# CurrentSensorInput.net
KiCad netlist of a schematic drawn in Altium Designer
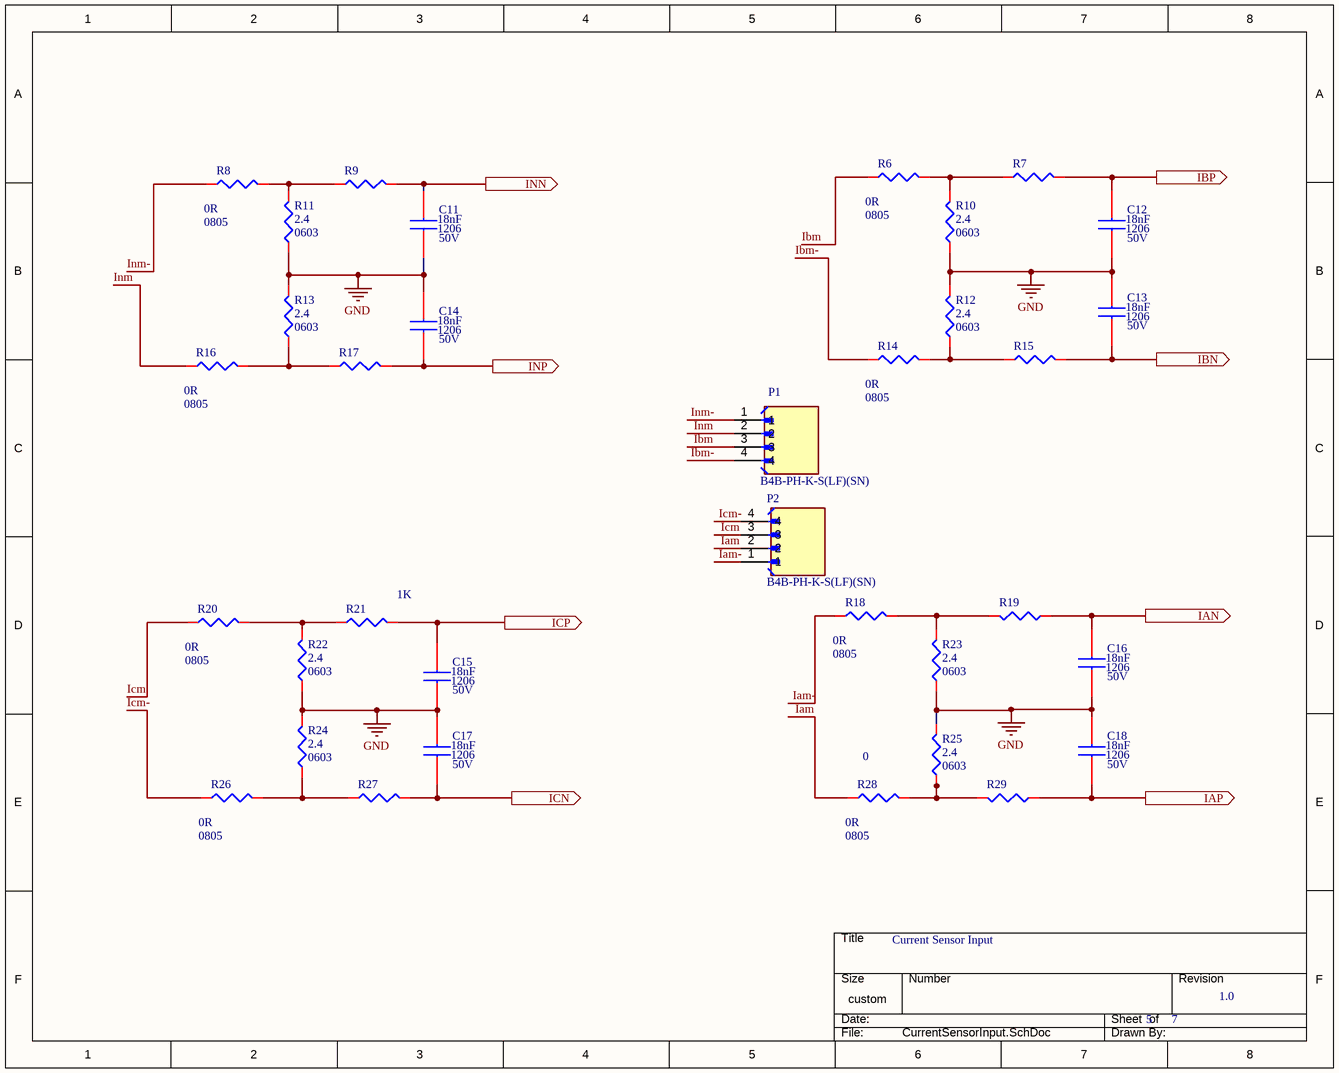
[diagram p0: CurrentSensorInput.SchDoc]

(export (version "E")
  (design (tool "Eeschema 10.0.6"))
  (components
    (comp (ref "C11")
      (value "C1206C183J5RACTU")
      (footprint "CAPC3316X180N")
      (description "Multilayer Ceramic Capacitors MLCC - SMD/SMT 50V 0.018uF X7R 1206 5%")
      (fields
        (field (name "MOUSER PART NUMBER") "80-C1206X224KARAUTO")
        (field (name "MANUFACTURER_PART_NUMBER") "C1206X224KARACAUTO")
        (field (name "SIZE") "1206")
        (field (name "CAPACITANCE") "18nF")
        (field (name "VOLTAGE") "50V")
      )
      (libsource (lib "C1206X224KARACAUTO") (part "C1206X224KARACAUTO"))
    )
    (comp (ref "C12")
      (value "C1206C183J5RACTU")
      (footprint "CAPC3316X180N")
      (description "Multilayer Ceramic Capacitors MLCC - SMD/SMT 50V 0.018uF X7R 1206 5%")
      (fields
        (field (name "MOUSER PART NUMBER") "80-C1206X224KARAUTO")
        (field (name "MANUFACTURER_PART_NUMBER") "C1206X224KARACAUTO")
        (field (name "SIZE") "1206")
        (field (name "CAPACITANCE") "18nF")
        (field (name "VOLTAGE") "50V")
      )
      (libsource (lib "C1206X224KARACAUTO") (part "C1206X224KARACAUTO"))
    )
    (comp (ref "C13")
      (value "C1206C183J5RACTU")
      (footprint "CAPC3316X180N")
      (description "Multilayer Ceramic Capacitors MLCC - SMD/SMT 50V 0.018uF X7R 1206 5%")
      (fields
        (field (name "MOUSER PART NUMBER") "80-C1206X224KARAUTO")
        (field (name "MANUFACTURER_PART_NUMBER") "C1206X224KARACAUTO")
        (field (name "SIZE") "1206")
        (field (name "CAPACITANCE") "18nF")
        (field (name "VOLTAGE") "50V")
      )
      (libsource (lib "C1206X224KARACAUTO") (part "C1206X224KARACAUTO"))
    )
    (comp (ref "C14")
      (value "C1206C183J5RACTU")
      (footprint "CAPC3316X180N")
      (description "Multilayer Ceramic Capacitors MLCC - SMD/SMT 50V 0.018uF X7R 1206 5%")
      (fields
        (field (name "MOUSER PART NUMBER") "80-C1206X224KARAUTO")
        (field (name "MANUFACTURER_PART_NUMBER") "C1206X224KARACAUTO")
        (field (name "SIZE") "1206")
        (field (name "CAPACITANCE") "18nF")
        (field (name "VOLTAGE") "50V")
      )
      (libsource (lib "C1206X224KARACAUTO") (part "C1206X224KARACAUTO"))
    )
    (comp (ref "C15")
      (value "C1206C183J5RACTU")
      (footprint "CAPC3316X180N")
      (description "Multilayer Ceramic Capacitors MLCC - SMD/SMT 50V 0.018uF X7R 1206 5%")
      (fields
        (field (name "MOUSER PART NUMBER") "80-C1206X224KARAUTO")
        (field (name "MANUFACTURER_PART_NUMBER") "C1206X224KARACAUTO")
        (field (name "SIZE") "1206")
        (field (name "CAPACITANCE") "18nF")
        (field (name "VOLTAGE") "50V")
      )
      (libsource (lib "C1206X224KARACAUTO") (part "C1206X224KARACAUTO"))
    )
    (comp (ref "C16")
      (value "C1206C183J5RACTU")
      (footprint "CAPC3316X180N")
      (description "Multilayer Ceramic Capacitors MLCC - SMD/SMT 50V 0.018uF X7R 1206 5%")
      (fields
        (field (name "MOUSER PART NUMBER") "80-C1206X224KARAUTO")
        (field (name "MANUFACTURER_PART_NUMBER") "C1206X224KARACAUTO")
        (field (name "SIZE") "1206")
        (field (name "CAPACITANCE") "18nF")
        (field (name "VOLTAGE") "50V")
      )
      (libsource (lib "C1206X224KARACAUTO") (part "C1206X224KARACAUTO"))
    )
    (comp (ref "C17")
      (value "C1206C183J5RACTU")
      (footprint "CAPC3316X180N")
      (description "Multilayer Ceramic Capacitors MLCC - SMD/SMT 50V 0.018uF X7R 1206 5%")
      (fields
        (field (name "MOUSER PART NUMBER") "80-C1206X224KARAUTO")
        (field (name "MANUFACTURER_PART_NUMBER") "C1206X224KARACAUTO")
        (field (name "SIZE") "1206")
        (field (name "CAPACITANCE") "18nF")
        (field (name "VOLTAGE") "50V")
      )
      (libsource (lib "C1206X224KARACAUTO") (part "C1206X224KARACAUTO"))
    )
    (comp (ref "C18")
      (value "C1206C183J5RACTU")
      (footprint "CAPC3316X180N")
      (description "Multilayer Ceramic Capacitors MLCC - SMD/SMT 50V 0.018uF X7R 1206 5%")
      (fields
        (field (name "MOUSER PART NUMBER") "80-C1206X224KARAUTO")
        (field (name "MANUFACTURER_PART_NUMBER") "C1206X224KARACAUTO")
        (field (name "SIZE") "1206")
        (field (name "CAPACITANCE") "18nF")
        (field (name "VOLTAGE") "50V")
      )
      (libsource (lib "C1206X224KARACAUTO") (part "C1206X224KARACAUTO"))
    )
    (comp (ref "P1")
      (value "B4B-PH-K-S(LF)(SN)")
      (footprint "JST_B4B-PH-K-S(LF)(SN)")
      (description "Connector Header Through Hole 4 position 0.079 (2.00mm)")
      (fields (field (name "MF") "JST"))
      (libsource (lib "University of Moratuwa") (part "B4B-PH-K-S(LF)(SN)"))
    )
    (comp (ref "P2")
      (value "B4B-PH-K-S(LF)(SN)")
      (footprint "JST_B4B-PH-K-S(LF)(SN)")
      (description "Connector Header Through Hole 4 position 0.079 (2.00mm)")
      (fields (field (name "MF") "JST"))
      (libsource (lib "") (part "B4B-PH-K-S(LF)(SN)_1"))
    )
    (comp (ref "R6")
      (value "WSL080500000ZEA9")
      (footprint "RESC2013X84N")
      (fields
        (field (name "MOUSER PART NUMBER") "71-WSL080500000ZEA9")
        (field (name "RESISTANCE") "0R")
        (field (name "SIZE") "0805")
      )
      (libsource (lib "WSL080500000ZEA9") (part "WSL080500000ZEA9"))
    )
    (comp (ref "R7")
      (value "ERA-6AED102V")
      (footprint "RESC2013X84N")
      (description "Thin Film Resistors - SMD 0805 1000ohms 25ppm 0.5% AEC-Q200")
      (fields (field (name "MOUSER PART NUMBER") "667-ERA-6AED102V"))
      (libsource (lib "ERA-6AED102V") (part "ERA-6AED102V"))
    )
    (comp (ref "R8")
      (value "WSL080500000ZEA9")
      (footprint "RESC2013X84N")
      (fields
        (field (name "MOUSER PART NUMBER") "71-WSL080500000ZEA9")
        (field (name "RESISTANCE") "0R")
        (field (name "SIZE") "0805")
      )
      (libsource (lib "WSL080500000ZEA9") (part "WSL080500000ZEA9"))
    )
    (comp (ref "R9")
      (value "ERA-6AED102V")
      (footprint "RESC2013X84N")
      (description "Thin Film Resistors - SMD 0805 1000ohms 25ppm 0.5% AEC-Q200")
      (fields (field (name "MOUSER PART NUMBER") "667-ERA-6AED102V"))
      (libsource (lib "ERA-6AED102V") (part "ERA-6AED102V"))
    )
    (comp (ref "R10")
      (value "CPF-A-0603B2K4E1")
      (footprint "RESC1608X55N")
      (description "Thick Film Resistors - SMD 2.4OHM 1% 1/2W 100PPM")
      (fields
        (field (name "MOUSER PART NUMBER") "71-WSL080500000ZEA9")
        (field (name "MANUFACTURER_PART_NUMBER") "WSL080500000ZEA9")
        (field (name "RESISTANCE") "2.4")
        (field (name "SIZE") "0603")
      )
      (libsource (lib "WSL080500000ZEA9") (part "WSL080500000ZEA9"))
    )
    (comp (ref "R11")
      (value "CPF-A-0603B2K4E1")
      (footprint "RESC1608X55N")
      (description "Thick Film Resistors - SMD 2.4OHM 1% 1/2W 100PPM")
      (fields
        (field (name "MOUSER PART NUMBER") "71-WSL080500000ZEA9")
        (field (name "MANUFACTURER_PART_NUMBER") "WSL080500000ZEA9")
        (field (name "RESISTANCE") "2.4")
        (field (name "SIZE") "0603")
      )
      (libsource (lib "WSL080500000ZEA9") (part "WSL080500000ZEA9"))
    )
    (comp (ref "R12")
      (value "CPF-A-0603B2K4E1")
      (footprint "RESC1608X55N")
      (description "Thick Film Resistors - SMD 2.4OHM 1% 1/2W 100PPM")
      (fields
        (field (name "MOUSER PART NUMBER") "71-WSL080500000ZEA9")
        (field (name "MANUFACTURER_PART_NUMBER") "WSL080500000ZEA9")
        (field (name "RESISTANCE") "2.4")
        (field (name "SIZE") "0603")
      )
      (libsource (lib "WSL080500000ZEA9") (part "WSL080500000ZEA9"))
    )
    (comp (ref "R13")
      (value "CPF-A-0603B2K4E1")
      (footprint "RESC1608X55N")
      (description "Thick Film Resistors - SMD 2.4OHM 1% 1/2W 100PPM")
      (fields
        (field (name "MOUSER PART NUMBER") "71-WSL080500000ZEA9")
        (field (name "MANUFACTURER_PART_NUMBER") "WSL080500000ZEA9")
        (field (name "RESISTANCE") "2.4")
        (field (name "SIZE") "0603")
      )
      (libsource (lib "WSL080500000ZEA9") (part "WSL080500000ZEA9"))
    )
    (comp (ref "R14")
      (value "WSL080500000ZEA9")
      (footprint "RESC2013X84N")
      (fields
        (field (name "MOUSER PART NUMBER") "71-WSL080500000ZEA9")
        (field (name "RESISTANCE") "0R")
        (field (name "SIZE") "0805")
      )
      (libsource (lib "WSL080500000ZEA9") (part "WSL080500000ZEA9"))
    )
    (comp (ref "R15")
      (value "ERA-6AED102V")
      (footprint "RESC2013X84N")
      (description "Thin Film Resistors - SMD 0805 1000ohms 25ppm 0.5% AEC-Q200")
      (fields (field (name "MOUSER PART NUMBER") "667-ERA-6AED102V"))
      (libsource (lib "ERA-6AED102V") (part "ERA-6AED102V"))
    )
    (comp (ref "R16")
      (value "WSL080500000ZEA9")
      (footprint "RESC2013X84N")
      (fields
        (field (name "MOUSER PART NUMBER") "71-WSL080500000ZEA9")
        (field (name "RESISTANCE") "0R")
        (field (name "SIZE") "0805")
      )
      (libsource (lib "WSL080500000ZEA9") (part "WSL080500000ZEA9"))
    )
    (comp (ref "R17")
      (value "ERA-6AED102V")
      (footprint "RESC2013X84N")
      (description "Thin Film Resistors - SMD 0805 1000ohms 25ppm 0.5% AEC-Q200")
      (fields (field (name "MOUSER PART NUMBER") "667-ERA-6AED102V"))
      (libsource (lib "ERA-6AED102V") (part "ERA-6AED102V"))
    )
    (comp (ref "R18")
      (value "WSL080500000ZEA9")
      (footprint "RESC2013X84N")
      (fields
        (field (name "MOUSER PART NUMBER") "71-WSL080500000ZEA9")
        (field (name "RESISTANCE") "0R")
        (field (name "SIZE") "0805")
      )
      (libsource (lib "WSL080500000ZEA9") (part "WSL080500000ZEA9"))
    )
    (comp (ref "R19")
      (value "ERA-6AED102V")
      (footprint "RESC2013X84N")
      (description "Thin Film Resistors - SMD 0805 1000ohms 25ppm 0.5% AEC-Q200")
      (fields (field (name "MOUSER PART NUMBER") "667-ERA-6AED102V"))
      (libsource (lib "ERA-6AED102V") (part "ERA-6AED102V"))
    )
    (comp (ref "R20")
      (value "WSL080500000ZEA9")
      (footprint "RESC2013X84N")
      (fields
        (field (name "MOUSER PART NUMBER") "71-WSL080500000ZEA9")
        (field (name "RESISTANCE") "0R")
        (field (name "SIZE") "0805")
      )
      (libsource (lib "WSL080500000ZEA9") (part "WSL080500000ZEA9"))
    )
    (comp (ref "R21")
      (value "ERA-6AED102V")
      (footprint "RESC2013X84N")
      (description "Thin Film Resistors - SMD 0805 1000ohms 25ppm 0.5% AEC-Q200")
      (fields (field (name "MOUSER PART NUMBER") "667-ERA-6AED102V"))
      (libsource (lib "ERA-6AED102V") (part "ERA-6AED102V"))
    )
    (comp (ref "R22")
      (value "CPF-A-0603B2K4E1")
      (footprint "RESC1608X55N")
      (description "Thick Film Resistors - SMD 2.4OHM 1% 1/2W 100PPM")
      (fields
        (field (name "MOUSER PART NUMBER") "71-WSL080500000ZEA9")
        (field (name "MANUFACTURER_PART_NUMBER") "WSL080500000ZEA9")
        (field (name "RESISTANCE") "2.4")
        (field (name "SIZE") "0603")
      )
      (libsource (lib "WSL080500000ZEA9") (part "WSL080500000ZEA9"))
    )
    (comp (ref "R23")
      (value "CPF-A-0603B2K4E1")
      (footprint "RESC1608X55N")
      (description "Thick Film Resistors - SMD 2.4OHM 1% 1/2W 100PPM")
      (fields
        (field (name "MOUSER PART NUMBER") "71-WSL080500000ZEA9")
        (field (name "MANUFACTURER_PART_NUMBER") "WSL080500000ZEA9")
        (field (name "RESISTANCE") "2.4")
        (field (name "SIZE") "0603")
      )
      (libsource (lib "WSL080500000ZEA9") (part "WSL080500000ZEA9"))
    )
    (comp (ref "R24")
      (value "CPF-A-0603B2K4E1")
      (footprint "RESC1608X55N")
      (description "Thick Film Resistors - SMD 2.4OHM 1% 1/2W 100PPM")
      (fields
        (field (name "MOUSER PART NUMBER") "71-WSL080500000ZEA9")
        (field (name "MANUFACTURER_PART_NUMBER") "WSL080500000ZEA9")
        (field (name "RESISTANCE") "2.4")
        (field (name "SIZE") "0603")
      )
      (libsource (lib "WSL080500000ZEA9") (part "WSL080500000ZEA9"))
    )
    (comp (ref "R25")
      (value "CPF-A-0603B2K4E1")
      (footprint "RESC1608X55N")
      (description "Thick Film Resistors - SMD 2.4OHM 1% 1/2W 100PPM")
      (fields
        (field (name "MOUSER PART NUMBER") "71-WSL080500000ZEA9")
        (field (name "MANUFACTURER_PART_NUMBER") "WSL080500000ZEA9")
        (field (name "RESISTANCE") "2.4")
        (field (name "SIZE") "0603")
      )
      (libsource (lib "WSL080500000ZEA9") (part "WSL080500000ZEA9"))
    )
    (comp (ref "R26")
      (value "WSL080500000ZEA9")
      (footprint "RESC2013X84N")
      (fields
        (field (name "MOUSER PART NUMBER") "71-WSL080500000ZEA9")
        (field (name "RESISTANCE") "0R")
        (field (name "SIZE") "0805")
      )
      (libsource (lib "WSL080500000ZEA9") (part "WSL080500000ZEA9"))
    )
    (comp (ref "R27")
      (value "ERA-6AED102V")
      (footprint "RESC2013X84N")
      (description "Thin Film Resistors - SMD 0805 1000ohms 25ppm 0.5% AEC-Q200")
      (fields (field (name "MOUSER PART NUMBER") "667-ERA-6AED102V"))
      (libsource (lib "ERA-6AED102V") (part "ERA-6AED102V"))
    )
    (comp (ref "R28")
      (value "WSL080500000ZEA9")
      (footprint "RESC2013X84N")
      (fields
        (field (name "MOUSER PART NUMBER") "71-WSL080500000ZEA9")
        (field (name "RESISTANCE") "0R")
        (field (name "SIZE") "0805")
      )
      (libsource (lib "WSL080500000ZEA9") (part "WSL080500000ZEA9"))
    )
    (comp (ref "R29")
      (value "ERA-6AED102V")
      (footprint "RESC2013X84N")
      (description "Thin Film Resistors - SMD 0805 1000ohms 25ppm 0.5% AEC-Q200")
      (fields (field (name "MOUSER PART NUMBER") "667-ERA-6AED102V"))
      (libsource (lib "ERA-6AED102V") (part "ERA-6AED102V"))
    )
  )
  (nets
    (net (code "1") (name "/IAN") (class "Default")
      (node (ref "C16") (pin "1") (pinfunction "1_1") (pintype "passive"))
      (node (ref "R19") (pin "2") (pinfunction "2_2") (pintype "passive"))
    )
    (net (code "2") (name "/IAP") (class "Default")
      (node (ref "C18") (pin "2") (pinfunction "2_2") (pintype "passive"))
      (node (ref "R29") (pin "2") (pinfunction "2_2") (pintype "passive"))
    )
    (net (code "3") (name "/IBN") (class "Default")
      (node (ref "C13") (pin "2") (pinfunction "2_2") (pintype "passive"))
      (node (ref "R15") (pin "1") (pinfunction "1_1") (pintype "passive"))
    )
    (net (code "4") (name "/IBP") (class "Default")
      (node (ref "C12") (pin "1") (pinfunction "1_1") (pintype "passive"))
      (node (ref "R7") (pin "1") (pinfunction "1_1") (pintype "passive"))
    )
    (net (code "5") (name "/ICN") (class "Default")
      (node (ref "C17") (pin "2") (pinfunction "2_2") (pintype "passive"))
      (node (ref "R27") (pin "1") (pinfunction "1_1") (pintype "passive"))
    )
    (net (code "6") (name "/ICP") (class "Default")
      (node (ref "C15") (pin "1") (pinfunction "1_1") (pintype "passive"))
      (node (ref "R21") (pin "1") (pinfunction "1_1") (pintype "passive"))
    )
    (net (code "7") (name "/INN") (class "Default")
      (node (ref "C11") (pin "1") (pinfunction "1_1") (pintype "passive"))
      (node (ref "R9") (pin "1") (pinfunction "1_1") (pintype "passive"))
    )
    (net (code "8") (name "/INP") (class "Default")
      (node (ref "C14") (pin "2") (pinfunction "2_2") (pintype "passive"))
      (node (ref "R17") (pin "1") (pinfunction "1_1") (pintype "passive"))
    )
    (net (code "9") (name "/Iam") (class "Default")
      (node (ref "P2") (pin "2") (pinfunction "2_2") (pintype "passive"))
      (node (ref "R28") (pin "2") (pinfunction "2_2") (pintype "passive"))
    )
    (net (code "10") (name "/Iam-") (class "Default")
      (node (ref "P2") (pin "1") (pinfunction "1_1") (pintype "passive"))
      (node (ref "R18") (pin "2") (pinfunction "2_2") (pintype "passive"))
    )
    (net (code "11") (name "/Ibm") (class "Default")
      (node (ref "P1") (pin "3") (pinfunction "3_3") (pintype "passive"))
      (node (ref "R6") (pin "2") (pinfunction "2_2") (pintype "passive"))
    )
    (net (code "12") (name "/Ibm-") (class "Default")
      (node (ref "P1") (pin "4") (pinfunction "4_4") (pintype "passive"))
      (node (ref "R14") (pin "2") (pinfunction "2_2") (pintype "passive"))
    )
    (net (code "13") (name "/Icm") (class "Default")
      (node (ref "P2") (pin "3") (pinfunction "3_3") (pintype "passive"))
      (node (ref "R20") (pin "2") (pinfunction "2_2") (pintype "passive"))
    )
    (net (code "14") (name "/Icm-") (class "Default")
      (node (ref "P2") (pin "4") (pinfunction "4_4") (pintype "passive"))
      (node (ref "R26") (pin "2") (pinfunction "2_2") (pintype "passive"))
    )
    (net (code "15") (name "/Inm") (class "Default")
      (node (ref "P1") (pin "2") (pinfunction "2_2") (pintype "passive"))
      (node (ref "R16") (pin "2") (pinfunction "2_2") (pintype "passive"))
    )
    (net (code "16") (name "/Inm-") (class "Default")
      (node (ref "P1") (pin "1") (pinfunction "1_1") (pintype "passive"))
      (node (ref "R8") (pin "2") (pinfunction "2_2") (pintype "passive"))
    )
    (net (code "17") (name "GND") (class "Default")
      (node (ref "C11") (pin "2") (pinfunction "2_2") (pintype "passive"))
      (node (ref "C12") (pin "2") (pinfunction "2_2") (pintype "passive"))
      (node (ref "C13") (pin "1") (pinfunction "1_1") (pintype "passive"))
      (node (ref "C14") (pin "1") (pinfunction "1_1") (pintype "passive"))
      (node (ref "C15") (pin "2") (pinfunction "2_2") (pintype "passive"))
      (node (ref "C16") (pin "2") (pinfunction "2_2") (pintype "passive"))
      (node (ref "C17") (pin "1") (pinfunction "1_1") (pintype "passive"))
      (node (ref "C18") (pin "1") (pinfunction "1_1") (pintype "passive"))
      (node (ref "R10") (pin "2") (pinfunction "2_2") (pintype "passive"))
      (node (ref "R11") (pin "2") (pinfunction "2_2") (pintype "passive"))
      (node (ref "R12") (pin "1") (pinfunction "1_1") (pintype "passive"))
      (node (ref "R13") (pin "1") (pinfunction "1_1") (pintype "passive"))
      (node (ref "R22") (pin "2") (pinfunction "2_2") (pintype "passive"))
      (node (ref "R23") (pin "2") (pinfunction "2_2") (pintype "passive"))
      (node (ref "R24") (pin "1") (pinfunction "1_1") (pintype "passive"))
      (node (ref "R25") (pin "1") (pinfunction "1_1") (pintype "passive"))
    )
    (net (code "18") (name "Net-(R10-Pad1)") (class "Default")
      (node (ref "R10") (pin "1") (pinfunction "1_1") (pintype "passive"))
      (node (ref "R6") (pin "1") (pinfunction "1_1") (pintype "passive"))
      (node (ref "R7") (pin "2") (pinfunction "2_2") (pintype "passive"))
    )
    (net (code "19") (name "Net-(R11-Pad1)") (class "Default")
      (node (ref "R11") (pin "1") (pinfunction "1_1") (pintype "passive"))
      (node (ref "R8") (pin "1") (pinfunction "1_1") (pintype "passive"))
      (node (ref "R9") (pin "2") (pinfunction "2_2") (pintype "passive"))
    )
    (net (code "20") (name "Net-(R12-Pad2)") (class "Default")
      (node (ref "R12") (pin "2") (pinfunction "2_2") (pintype "passive"))
      (node (ref "R14") (pin "1") (pinfunction "1_1") (pintype "passive"))
      (node (ref "R15") (pin "2") (pinfunction "2_2") (pintype "passive"))
    )
    (net (code "21") (name "Net-(R13-Pad2)") (class "Default")
      (node (ref "R13") (pin "2") (pinfunction "2_2") (pintype "passive"))
      (node (ref "R16") (pin "1") (pinfunction "1_1") (pintype "passive"))
      (node (ref "R17") (pin "2") (pinfunction "2_2") (pintype "passive"))
    )
    (net (code "22") (name "Net-(R18-Pad1)") (class "Default")
      (node (ref "R18") (pin "1") (pinfunction "1_1") (pintype "passive"))
      (node (ref "R19") (pin "1") (pinfunction "1_1") (pintype "passive"))
      (node (ref "R23") (pin "1") (pinfunction "1_1") (pintype "passive"))
    )
    (net (code "23") (name "Net-(R20-Pad1)") (class "Default")
      (node (ref "R20") (pin "1") (pinfunction "1_1") (pintype "passive"))
      (node (ref "R21") (pin "2") (pinfunction "2_2") (pintype "passive"))
      (node (ref "R22") (pin "1") (pinfunction "1_1") (pintype "passive"))
    )
    (net (code "24") (name "Net-(R24-Pad2)") (class "Default")
      (node (ref "R24") (pin "2") (pinfunction "2_2") (pintype "passive"))
      (node (ref "R26") (pin "1") (pinfunction "1_1") (pintype "passive"))
      (node (ref "R27") (pin "2") (pinfunction "2_2") (pintype "passive"))
    )
    (net (code "25") (name "Net-(R25-Pad2)") (class "Default")
      (node (ref "R25") (pin "2") (pinfunction "2_2") (pintype "passive"))
      (node (ref "R28") (pin "1") (pinfunction "1_1") (pintype "passive"))
      (node (ref "R29") (pin "1") (pinfunction "1_1") (pintype "passive"))
    )
  )
)
